# Flipper.net
KiCad netlist of a schematic drawn in EasyEDA
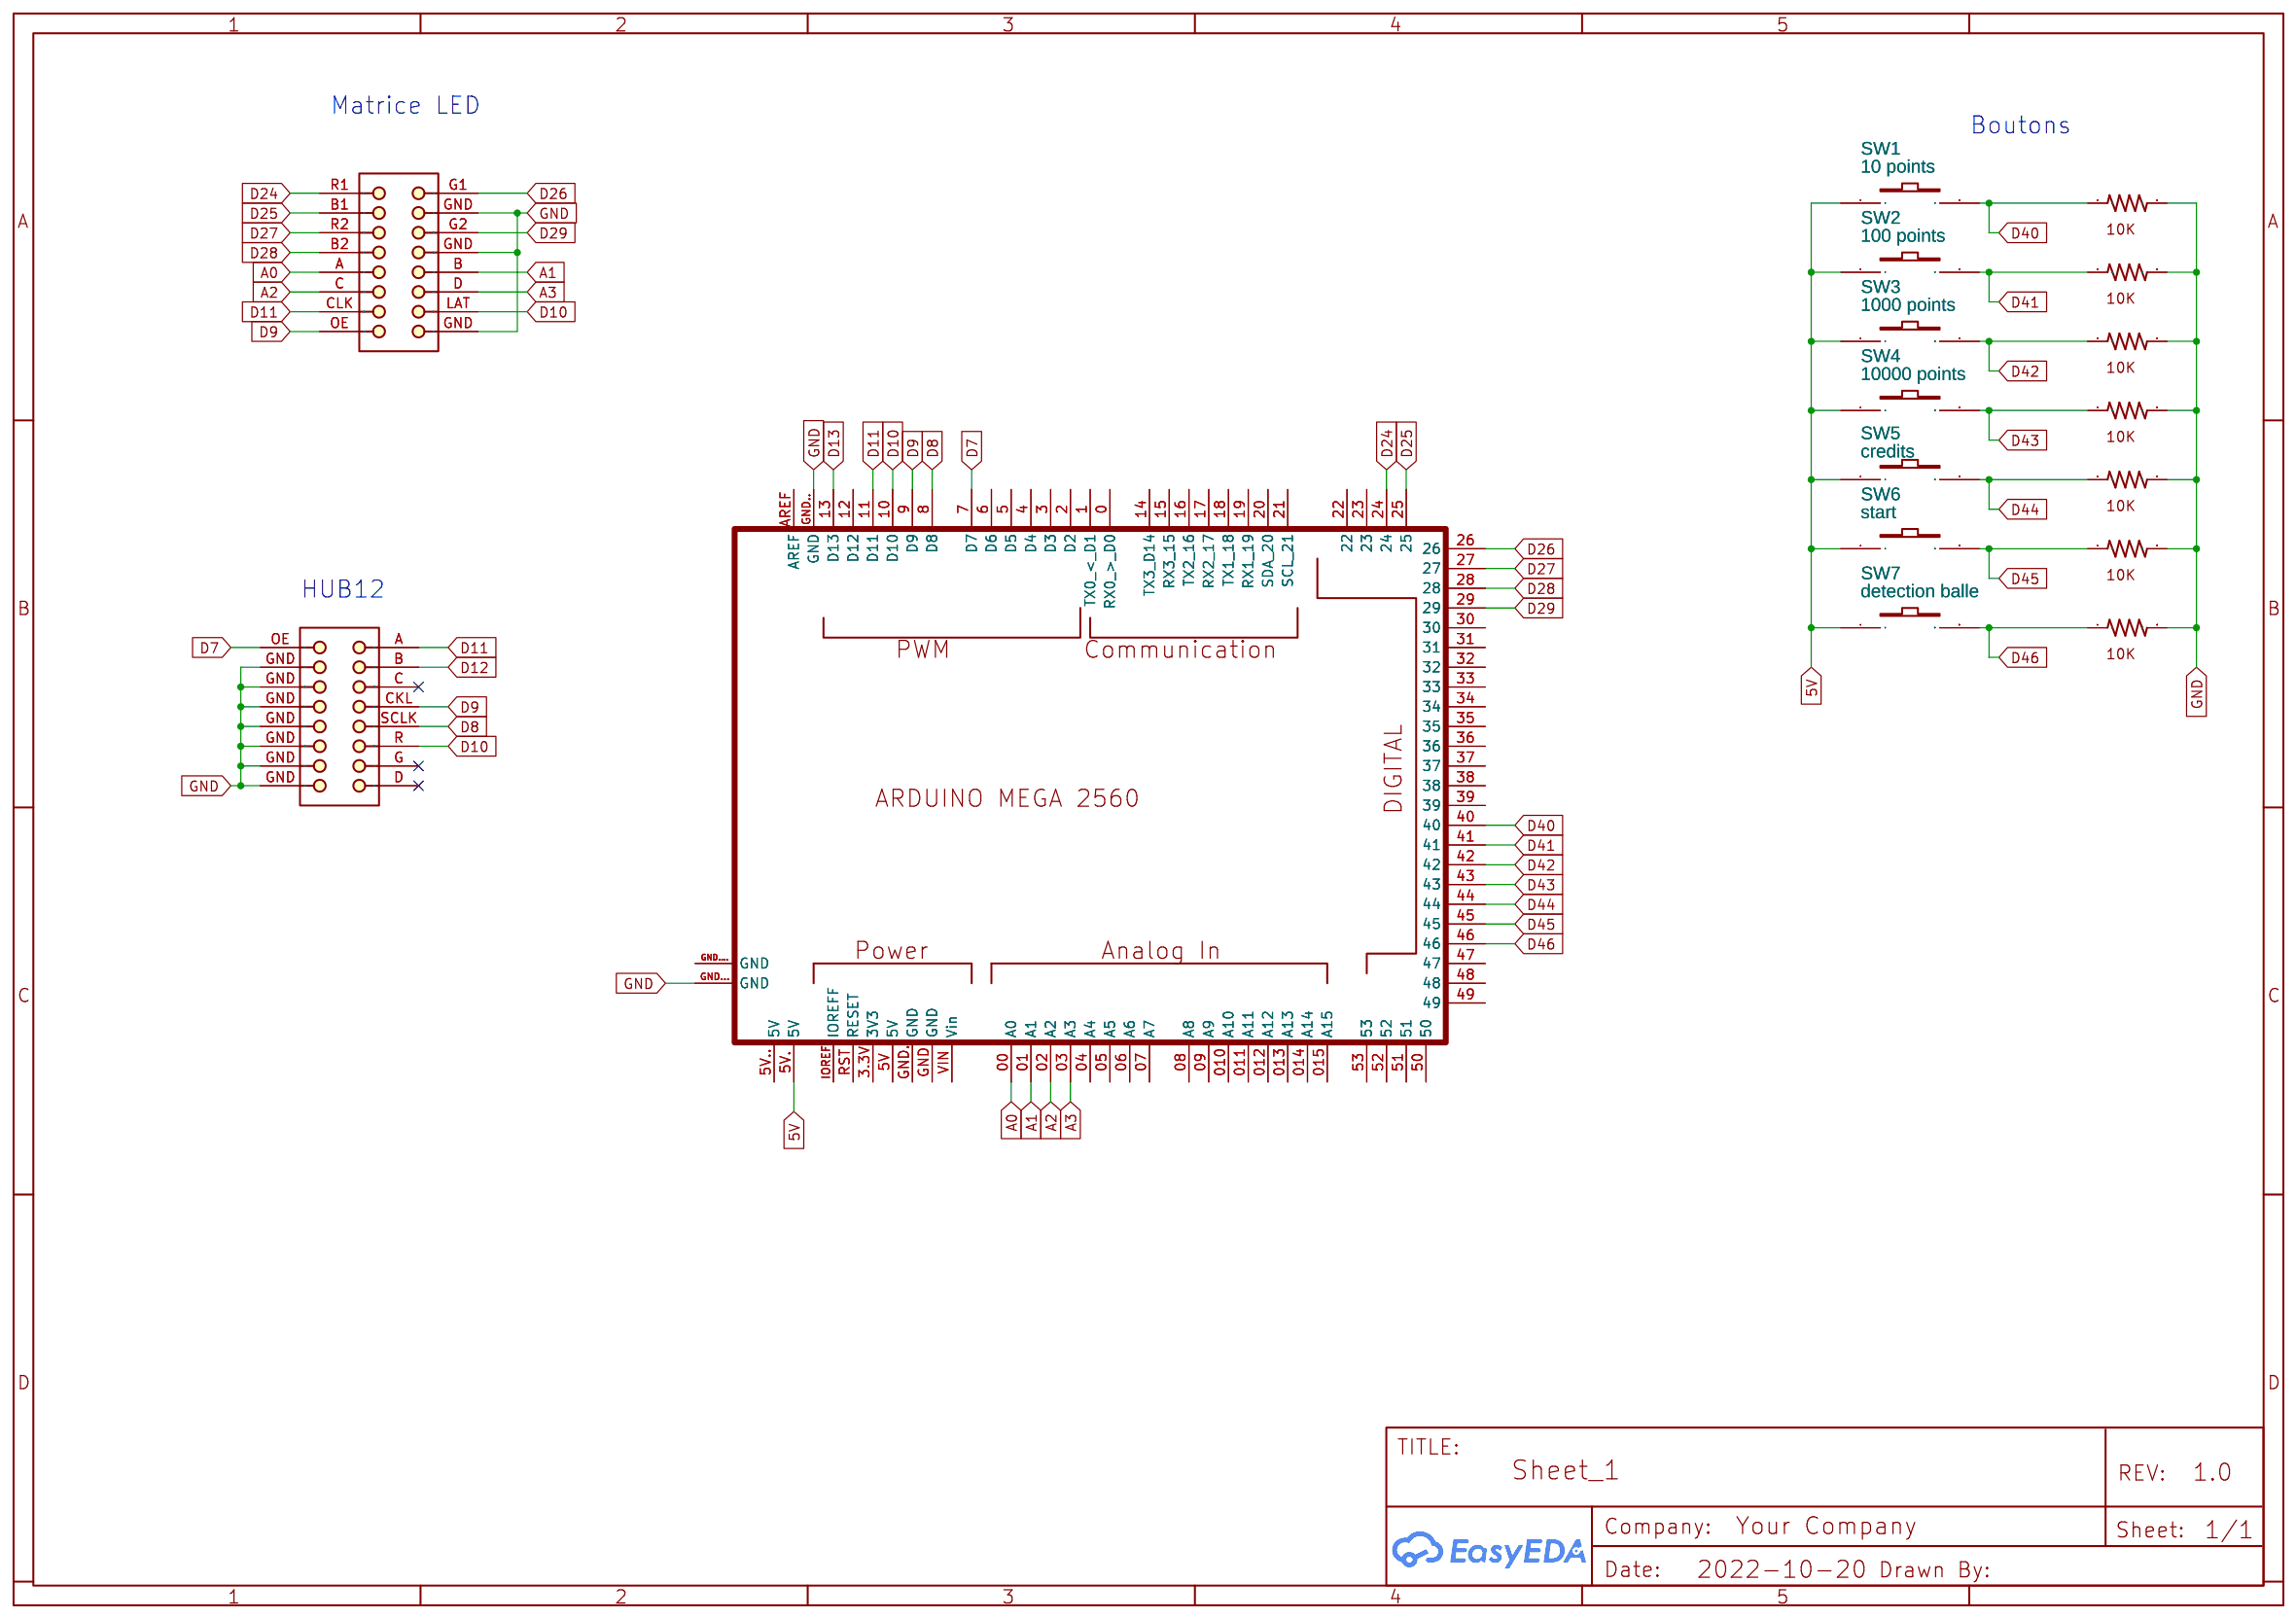
[diagram p0: schematic sheet]

(export (version "E")
  (design (tool "Eeschema 10.0.6"))
  (components
    (comp (ref "R1") (value "10K-OHM-RESISTOR") (libsource (lib "") (part "10K-OHM-RESISTOR")))
    (comp (ref "R2") (value "10K-OHM-RESISTOR") (libsource (lib "") (part "10K-OHM-RESISTOR")))
    (comp (ref "R3") (value "10K-OHM-RESISTOR") (libsource (lib "") (part "10K-OHM-RESISTOR")))
    (comp (ref "R4") (value "10K-OHM-RESISTOR") (libsource (lib "") (part "10K-OHM-RESISTOR")))
    (comp (ref "R5") (value "10K-OHM-RESISTOR") (libsource (lib "") (part "10K-OHM-RESISTOR")))
    (comp (ref "R6") (value "10K-OHM-RESISTOR") (libsource (lib "") (part "10K-OHM-RESISTOR")))
    (comp (ref "R7") (value "10K-OHM-RESISTOR") (libsource (lib "") (part "10K-OHM-RESISTOR")))
    (comp (ref "SMD1") (value "Matrice LED") (libsource (lib "") (part "09_18_516_6329_1")))
    (comp (ref "SMD2") (value "Matrice LED") (libsource (lib "") (part "09_18_516_6329")))
    (comp (ref "SW1") (value "10 points") (libsource (lib "") (part "Pushbutton-02")))
    (comp (ref "SW2") (value "100 points") (libsource (lib "") (part "Pushbutton-02")))
    (comp (ref "SW3") (value "1000 points") (libsource (lib "") (part "Pushbutton-02")))
    (comp (ref "SW4") (value "10000 points") (libsource (lib "") (part "Pushbutton-02")))
    (comp (ref "SW5") (value "credits") (libsource (lib "") (part "Pushbutton-02")))
    (comp (ref "SW6") (value "start") (libsource (lib "") (part "Pushbutton-02")))
    (comp (ref "SW7") (value "detection balle") (libsource (lib "") (part "Pushbutton-02")))
    (comp (ref "U1")
      (value "ARDUINO MEGA 2560 R3 V1.0")
      (libsource (lib "") (part "ARDUINO MEGA 2560 R3 V1.0"))
    )
  )
  (nets
    (net (code "1") (name "5V") (class "Default")
      (node (ref "SW1") (pin "1") (pinfunction "1_1") (pintype "input"))
      (node (ref "SW2") (pin "1") (pinfunction "1_1") (pintype "input"))
      (node (ref "SW3") (pin "1") (pinfunction "1_1") (pintype "input"))
      (node (ref "SW4") (pin "1") (pinfunction "1_1") (pintype "input"))
      (node (ref "SW5") (pin "1") (pinfunction "1_1") (pintype "input"))
      (node (ref "SW6") (pin "1") (pinfunction "1_1") (pintype "input"))
      (node (ref "SW7") (pin "1") (pinfunction "1_1") (pintype "input"))
      (node (ref "U1") (pin "5V.") (pinfunction "5V_5V.") (pintype "unspecified"))
    )
    (net (code "2") (name "A0") (class "Default")
      (node (ref "SMD1") (pin "A") (pinfunction "9_A") (pintype "unspecified"))
      (node (ref "U1") (pin "00") (pinfunction "A0_00") (pintype "unspecified"))
    )
    (net (code "3") (name "A1") (class "Default")
      (node (ref "SMD1") (pin "B") (pinfunction "10_B") (pintype "unspecified"))
      (node (ref "U1") (pin "01") (pinfunction "A1_01") (pintype "unspecified"))
    )
    (net (code "4") (name "A2") (class "Default")
      (node (ref "SMD1") (pin "C") (pinfunction "11_C") (pintype "unspecified"))
      (node (ref "U1") (pin "02") (pinfunction "A2_02") (pintype "unspecified"))
    )
    (net (code "5") (name "A3") (class "Default")
      (node (ref "SMD1") (pin "D") (pinfunction "12_D") (pintype "unspecified"))
      (node (ref "U1") (pin "03") (pinfunction "A3_03") (pintype "unspecified"))
    )
    (net (code "6") (name "D7") (class "Default")
      (node (ref "SMD2") (pin "OE") (pinfunction "1_OE") (pintype "unspecified"))
      (node (ref "U1") (pin "7") (pinfunction "D7_7") (pintype "unspecified"))
    )
    (net (code "7") (name "D8") (class "Default")
      (node (ref "SMD2") (pin "SCLK") (pinfunction "10_SCLK") (pintype "unspecified"))
      (node (ref "U1") (pin "8") (pinfunction "D8_8") (pintype "unspecified"))
    )
    (net (code "8") (name "D9") (class "Default")
      (node (ref "SMD1") (pin "OE") (pinfunction "15_OE") (pintype "unspecified"))
      (node (ref "SMD2") (pin "CKL") (pinfunction "8_CKL") (pintype "unspecified"))
      (node (ref "U1") (pin "9") (pinfunction "D9_9") (pintype "unspecified"))
    )
    (net (code "9") (name "D10") (class "Default")
      (node (ref "SMD1") (pin "LAT") (pinfunction "14_LAT") (pintype "unspecified"))
      (node (ref "SMD2") (pin "R") (pinfunction "12_R") (pintype "unspecified"))
      (node (ref "U1") (pin "10") (pinfunction "D10_10") (pintype "unspecified"))
    )
    (net (code "10") (name "D11") (class "Default")
      (node (ref "SMD1") (pin "CLK") (pinfunction "13_CLK") (pintype "unspecified"))
      (node (ref "SMD2") (pin "A") (pinfunction "2_A") (pintype "unspecified"))
      (node (ref "U1") (pin "11") (pinfunction "D11_11") (pintype "unspecified"))
    )
    (net (code "11") (name "D12") (class "Default")
      (node (ref "SMD2") (pin "B") (pinfunction "4_B") (pintype "unspecified"))
    )
    (net (code "12") (name "D13") (class "Default")
      (node (ref "U1") (pin "13") (pinfunction "D13_13") (pintype "unspecified"))
    )
    (net (code "13") (name "D24") (class "Default")
      (node (ref "SMD1") (pin "R1") (pinfunction "1_R1") (pintype "unspecified"))
      (node (ref "U1") (pin "24") (pinfunction "24_24") (pintype "unspecified"))
    )
    (net (code "14") (name "D25") (class "Default")
      (node (ref "SMD1") (pin "B1") (pinfunction "3_B1") (pintype "unspecified"))
      (node (ref "U1") (pin "25") (pinfunction "25_25") (pintype "unspecified"))
    )
    (net (code "15") (name "D26") (class "Default")
      (node (ref "SMD1") (pin "G1") (pinfunction "2_G1") (pintype "unspecified"))
      (node (ref "U1") (pin "26") (pinfunction "26_26") (pintype "unspecified"))
    )
    (net (code "16") (name "D27") (class "Default")
      (node (ref "SMD1") (pin "R2") (pinfunction "5_R2") (pintype "unspecified"))
      (node (ref "U1") (pin "27") (pinfunction "27_27") (pintype "unspecified"))
    )
    (net (code "17") (name "D28") (class "Default")
      (node (ref "SMD1") (pin "B2") (pinfunction "7_B2") (pintype "unspecified"))
      (node (ref "U1") (pin "28") (pinfunction "28_28") (pintype "unspecified"))
    )
    (net (code "18") (name "D29") (class "Default")
      (node (ref "SMD1") (pin "G2") (pinfunction "6_G2") (pintype "unspecified"))
      (node (ref "U1") (pin "29") (pinfunction "29_29") (pintype "unspecified"))
    )
    (net (code "19") (name "D40") (class "Default")
      (node (ref "R1") (pin "1") (pinfunction "1_1") (pintype "bidirectional"))
      (node (ref "SW1") (pin "2") (pinfunction "2_2") (pintype "input"))
      (node (ref "U1") (pin "40") (pinfunction "40_40") (pintype "unspecified"))
    )
    (net (code "20") (name "D41") (class "Default")
      (node (ref "R2") (pin "1") (pinfunction "1_1") (pintype "bidirectional"))
      (node (ref "SW2") (pin "2") (pinfunction "2_2") (pintype "input"))
      (node (ref "U1") (pin "41") (pinfunction "41_41") (pintype "unspecified"))
    )
    (net (code "21") (name "D42") (class "Default")
      (node (ref "R3") (pin "1") (pinfunction "1_1") (pintype "bidirectional"))
      (node (ref "SW3") (pin "2") (pinfunction "2_2") (pintype "input"))
      (node (ref "U1") (pin "42") (pinfunction "42_42") (pintype "unspecified"))
    )
    (net (code "22") (name "D43") (class "Default")
      (node (ref "R4") (pin "1") (pinfunction "1_1") (pintype "bidirectional"))
      (node (ref "SW4") (pin "2") (pinfunction "2_2") (pintype "input"))
      (node (ref "U1") (pin "43") (pinfunction "43_43") (pintype "unspecified"))
    )
    (net (code "23") (name "D44") (class "Default")
      (node (ref "R5") (pin "1") (pinfunction "1_1") (pintype "bidirectional"))
      (node (ref "SW5") (pin "2") (pinfunction "2_2") (pintype "input"))
      (node (ref "U1") (pin "44") (pinfunction "44_44") (pintype "unspecified"))
    )
    (net (code "24") (name "D45") (class "Default")
      (node (ref "R6") (pin "1") (pinfunction "1_1") (pintype "bidirectional"))
      (node (ref "SW6") (pin "2") (pinfunction "2_2") (pintype "input"))
      (node (ref "U1") (pin "45") (pinfunction "45_45") (pintype "unspecified"))
    )
    (net (code "25") (name "D46") (class "Default")
      (node (ref "R7") (pin "1") (pinfunction "1_1") (pintype "bidirectional"))
      (node (ref "SW7") (pin "2") (pinfunction "2_2") (pintype "input"))
      (node (ref "U1") (pin "46") (pinfunction "46_46") (pintype "unspecified"))
    )
    (net (code "26") (name "GND") (class "Default")
      (node (ref "R1") (pin "2") (pinfunction "2_2") (pintype "bidirectional"))
      (node (ref "R2") (pin "2") (pinfunction "2_2") (pintype "bidirectional"))
      (node (ref "R3") (pin "2") (pinfunction "2_2") (pintype "bidirectional"))
      (node (ref "R4") (pin "2") (pinfunction "2_2") (pintype "bidirectional"))
      (node (ref "R5") (pin "2") (pinfunction "2_2") (pintype "bidirectional"))
      (node (ref "R6") (pin "2") (pinfunction "2_2") (pintype "bidirectional"))
      (node (ref "R7") (pin "2") (pinfunction "2_2") (pintype "bidirectional"))
      (node (ref "SMD1") (pin "GND") (pinfunction "16_GND") (pintype "unspecified"))
      (node (ref "SMD2") (pin "GND") (pinfunction "15_GND") (pintype "unspecified"))
      (node (ref "U1") (pin "GND..") (pinfunction "GND_GND..") (pintype "unspecified"))
      (node (ref "U1") (pin "GND...") (pinfunction "GND_GND...") (pintype "unspecified"))
    )
    (net (code "27") (name "unconnected-(SMD2-6-PadC)") (class "Default")
      (node (ref "SMD2") (pin "C") (pinfunction "6_C") (pintype "unspecified+no_connect"))
    )
    (net (code "28") (name "unconnected-(SMD2-14-PadG)") (class "Default")
      (node (ref "SMD2") (pin "G") (pinfunction "14_G") (pintype "unspecified+no_connect"))
    )
    (net (code "29") (name "unconnected-(SMD2-16-PadD)") (class "Default")
      (node (ref "SMD2") (pin "D") (pinfunction "16_D") (pintype "unspecified+no_connect"))
    )
    (net (code "30") (name "unconnected-(U1-3V3-Pad3.3V)") (class "Default")
      (node (ref "U1") (pin "3.3V") (pinfunction "3V3_3.3V") (pintype "unspecified"))
    )
    (net (code "31") (name "unconnected-(U1-5V-Pad5V..)") (class "Default")
      (node (ref "U1") (pin "5V..") (pinfunction "5V_5V..") (pintype "unspecified"))
    )
    (net (code "32") (name "unconnected-(U1-A4-Pad04)") (class "Default")
      (node (ref "U1") (pin "04") (pinfunction "A4_04") (pintype "unspecified"))
    )
    (net (code "33") (name "unconnected-(U1-A5-Pad05)") (class "Default")
      (node (ref "U1") (pin "05") (pinfunction "A5_05") (pintype "unspecified"))
    )
    (net (code "34") (name "unconnected-(U1-A6-Pad06)") (class "Default")
      (node (ref "U1") (pin "06") (pinfunction "A6_06") (pintype "unspecified"))
    )
    (net (code "35") (name "unconnected-(U1-A7-Pad07)") (class "Default")
      (node (ref "U1") (pin "07") (pinfunction "A7_07") (pintype "unspecified"))
    )
    (net (code "36") (name "unconnected-(U1-A8-Pad08)") (class "Default")
      (node (ref "U1") (pin "08") (pinfunction "A8_08") (pintype "unspecified"))
    )
    (net (code "37") (name "unconnected-(U1-A9-Pad09)") (class "Default")
      (node (ref "U1") (pin "09") (pinfunction "A9_09") (pintype "unspecified"))
    )
    (net (code "38") (name "unconnected-(U1-A10-Pad010)") (class "Default")
      (node (ref "U1") (pin "010") (pinfunction "A10_010") (pintype "unspecified"))
    )
    (net (code "39") (name "unconnected-(U1-A11-Pad011)") (class "Default")
      (node (ref "U1") (pin "011") (pinfunction "A11_011") (pintype "unspecified"))
    )
    (net (code "40") (name "unconnected-(U1-A12-Pad012)") (class "Default")
      (node (ref "U1") (pin "012") (pinfunction "A12_012") (pintype "unspecified"))
    )
    (net (code "41") (name "unconnected-(U1-A13-Pad013)") (class "Default")
      (node (ref "U1") (pin "013") (pinfunction "A13_013") (pintype "unspecified"))
    )
    (net (code "42") (name "unconnected-(U1-A14-Pad014)") (class "Default")
      (node (ref "U1") (pin "014") (pinfunction "A14_014") (pintype "unspecified"))
    )
    (net (code "43") (name "unconnected-(U1-A15-Pad015)") (class "Default")
      (node (ref "U1") (pin "015") (pinfunction "A15_015") (pintype "unspecified"))
    )
    (net (code "44") (name "unconnected-(U1-D2-Pad2)") (class "Default")
      (node (ref "U1") (pin "2") (pinfunction "D2_2") (pintype "unspecified"))
    )
    (net (code "45") (name "unconnected-(U1-D3-Pad3)") (class "Default")
      (node (ref "U1") (pin "3") (pinfunction "D3_3") (pintype "unspecified"))
    )
    (net (code "46") (name "unconnected-(U1-D4-Pad4)") (class "Default")
      (node (ref "U1") (pin "4") (pinfunction "D4_4") (pintype "unspecified"))
    )
    (net (code "47") (name "unconnected-(U1-D5-Pad5)") (class "Default")
      (node (ref "U1") (pin "5") (pinfunction "D5_5") (pintype "unspecified"))
    )
    (net (code "48") (name "unconnected-(U1-D6-Pad6)") (class "Default")
      (node (ref "U1") (pin "6") (pinfunction "D6_6") (pintype "unspecified"))
    )
    (net (code "49") (name "unconnected-(U1-D12-Pad12)") (class "Default")
      (node (ref "U1") (pin "12") (pinfunction "D12_12") (pintype "unspecified"))
    )
    (net (code "50") (name "unconnected-(U1-GND-PadGND.)") (class "Default")
      (node (ref "U1") (pin "GND.") (pinfunction "GND_GND.") (pintype "unspecified"))
    )
    (net (code "51") (name "unconnected-(U1-GND-PadGND....)") (class "Default")
      (node (ref "U1") (pin "GND....") (pinfunction "GND_GND....") (pintype "unspecified"))
    )
    (net (code "52") (name "unconnected-(U1-IOREFF-PadIOREF)") (class "Default")
      (node (ref "U1") (pin "IOREF") (pinfunction "IOREFF_IOREF") (pintype "unspecified"))
    )
    (net (code "53") (name "unconnected-(U1-Pad5V)") (class "Default")
      (node (ref "U1") (pin "5V") (pinfunction "5V_5V") (pintype "unspecified"))
    )
    (net (code "54") (name "unconnected-(U1-Pad22)") (class "Default")
      (node (ref "U1") (pin "22") (pinfunction "22_22") (pintype "unspecified"))
    )
    (net (code "55") (name "unconnected-(U1-Pad23)") (class "Default")
      (node (ref "U1") (pin "23") (pinfunction "23_23") (pintype "unspecified"))
    )
    (net (code "56") (name "unconnected-(U1-Pad30)") (class "Default")
      (node (ref "U1") (pin "30") (pinfunction "30_30") (pintype "unspecified"))
    )
    (net (code "57") (name "unconnected-(U1-Pad31)") (class "Default")
      (node (ref "U1") (pin "31") (pinfunction "31_31") (pintype "unspecified"))
    )
    (net (code "58") (name "unconnected-(U1-Pad32)") (class "Default")
      (node (ref "U1") (pin "32") (pinfunction "32_32") (pintype "unspecified"))
    )
    (net (code "59") (name "unconnected-(U1-Pad33)") (class "Default")
      (node (ref "U1") (pin "33") (pinfunction "33_33") (pintype "unspecified"))
    )
    (net (code "60") (name "unconnected-(U1-Pad34)") (class "Default")
      (node (ref "U1") (pin "34") (pinfunction "34_34") (pintype "unspecified"))
    )
    (net (code "61") (name "unconnected-(U1-Pad35)") (class "Default")
      (node (ref "U1") (pin "35") (pinfunction "35_35") (pintype "unspecified"))
    )
    (net (code "62") (name "unconnected-(U1-Pad36)") (class "Default")
      (node (ref "U1") (pin "36") (pinfunction "36_36") (pintype "unspecified"))
    )
    (net (code "63") (name "unconnected-(U1-Pad37)") (class "Default")
      (node (ref "U1") (pin "37") (pinfunction "37_37") (pintype "unspecified"))
    )
    (net (code "64") (name "unconnected-(U1-Pad38)") (class "Default")
      (node (ref "U1") (pin "38") (pinfunction "38_38") (pintype "unspecified"))
    )
    (net (code "65") (name "unconnected-(U1-Pad39)") (class "Default")
      (node (ref "U1") (pin "39") (pinfunction "39_39") (pintype "unspecified"))
    )
    (net (code "66") (name "unconnected-(U1-Pad47)") (class "Default")
      (node (ref "U1") (pin "47") (pinfunction "47_47") (pintype "unspecified"))
    )
    (net (code "67") (name "unconnected-(U1-Pad48)") (class "Default")
      (node (ref "U1") (pin "48") (pinfunction "48_48") (pintype "unspecified"))
    )
    (net (code "68") (name "unconnected-(U1-Pad49)") (class "Default")
      (node (ref "U1") (pin "49") (pinfunction "49_49") (pintype "unspecified"))
    )
    (net (code "69") (name "unconnected-(U1-Pad50)") (class "Default")
      (node (ref "U1") (pin "50") (pinfunction "50_50") (pintype "unspecified"))
    )
    (net (code "70") (name "unconnected-(U1-Pad51)") (class "Default")
      (node (ref "U1") (pin "51") (pinfunction "51_51") (pintype "unspecified"))
    )
    (net (code "71") (name "unconnected-(U1-Pad52)") (class "Default")
      (node (ref "U1") (pin "52") (pinfunction "52_52") (pintype "unspecified"))
    )
    (net (code "72") (name "unconnected-(U1-Pad53)") (class "Default")
      (node (ref "U1") (pin "53") (pinfunction "53_53") (pintype "unspecified"))
    )
    (net (code "73") (name "unconnected-(U1-PadAREF)") (class "Default")
      (node (ref "U1") (pin "AREF") (pinfunction "AREF_AREF") (pintype "unspecified"))
    )
    (net (code "74") (name "unconnected-(U1-PadGND)") (class "Default")
      (node (ref "U1") (pin "GND") (pinfunction "GND_GND") (pintype "unspecified"))
    )
    (net (code "75") (name "unconnected-(U1-RESET-PadRST)") (class "Default")
      (node (ref "U1") (pin "RST") (pinfunction "RESET_RST") (pintype "unspecified"))
    )
    (net (code "76") (name "unconnected-(U1-RX0_>_D0-Pad0)") (class "Default")
      (node (ref "U1") (pin "0") (pinfunction "RX0_>_D0_0") (pintype "unspecified"))
    )
    (net (code "77") (name "unconnected-(U1-RX1_19-Pad19)") (class "Default")
      (node (ref "U1") (pin "19") (pinfunction "RX1_19_19") (pintype "unspecified"))
    )
    (net (code "78") (name "unconnected-(U1-RX2_17-Pad17)") (class "Default")
      (node (ref "U1") (pin "17") (pinfunction "RX2_17_17") (pintype "unspecified"))
    )
    (net (code "79") (name "unconnected-(U1-RX3_15-Pad15)") (class "Default")
      (node (ref "U1") (pin "15") (pinfunction "RX3_15_15") (pintype "unspecified"))
    )
    (net (code "80") (name "unconnected-(U1-SCL_21-Pad21)") (class "Default")
      (node (ref "U1") (pin "21") (pinfunction "SCL_21_21") (pintype "unspecified"))
    )
    (net (code "81") (name "unconnected-(U1-SDA_20-Pad20)") (class "Default")
      (node (ref "U1") (pin "20") (pinfunction "SDA_20_20") (pintype "unspecified"))
    )
    (net (code "82") (name "unconnected-(U1-TX0_<_D1-Pad1)") (class "Default")
      (node (ref "U1") (pin "1") (pinfunction "TX0_<_D1_1") (pintype "unspecified"))
    )
    (net (code "83") (name "unconnected-(U1-TX1_18-Pad18)") (class "Default")
      (node (ref "U1") (pin "18") (pinfunction "TX1_18_18") (pintype "unspecified"))
    )
    (net (code "84") (name "unconnected-(U1-TX2_16-Pad16)") (class "Default")
      (node (ref "U1") (pin "16") (pinfunction "TX2_16_16") (pintype "unspecified"))
    )
    (net (code "85") (name "unconnected-(U1-TX3_D14-Pad14)") (class "Default")
      (node (ref "U1") (pin "14") (pinfunction "TX3_D14_14") (pintype "unspecified"))
    )
    (net (code "86") (name "unconnected-(U1-Vin-PadVIN)") (class "Default")
      (node (ref "U1") (pin "VIN") (pinfunction "Vin_VIN") (pintype "unspecified"))
    )
  )
)
